# design.net
KiCad netlist of a schematic drawn in Altium Designer
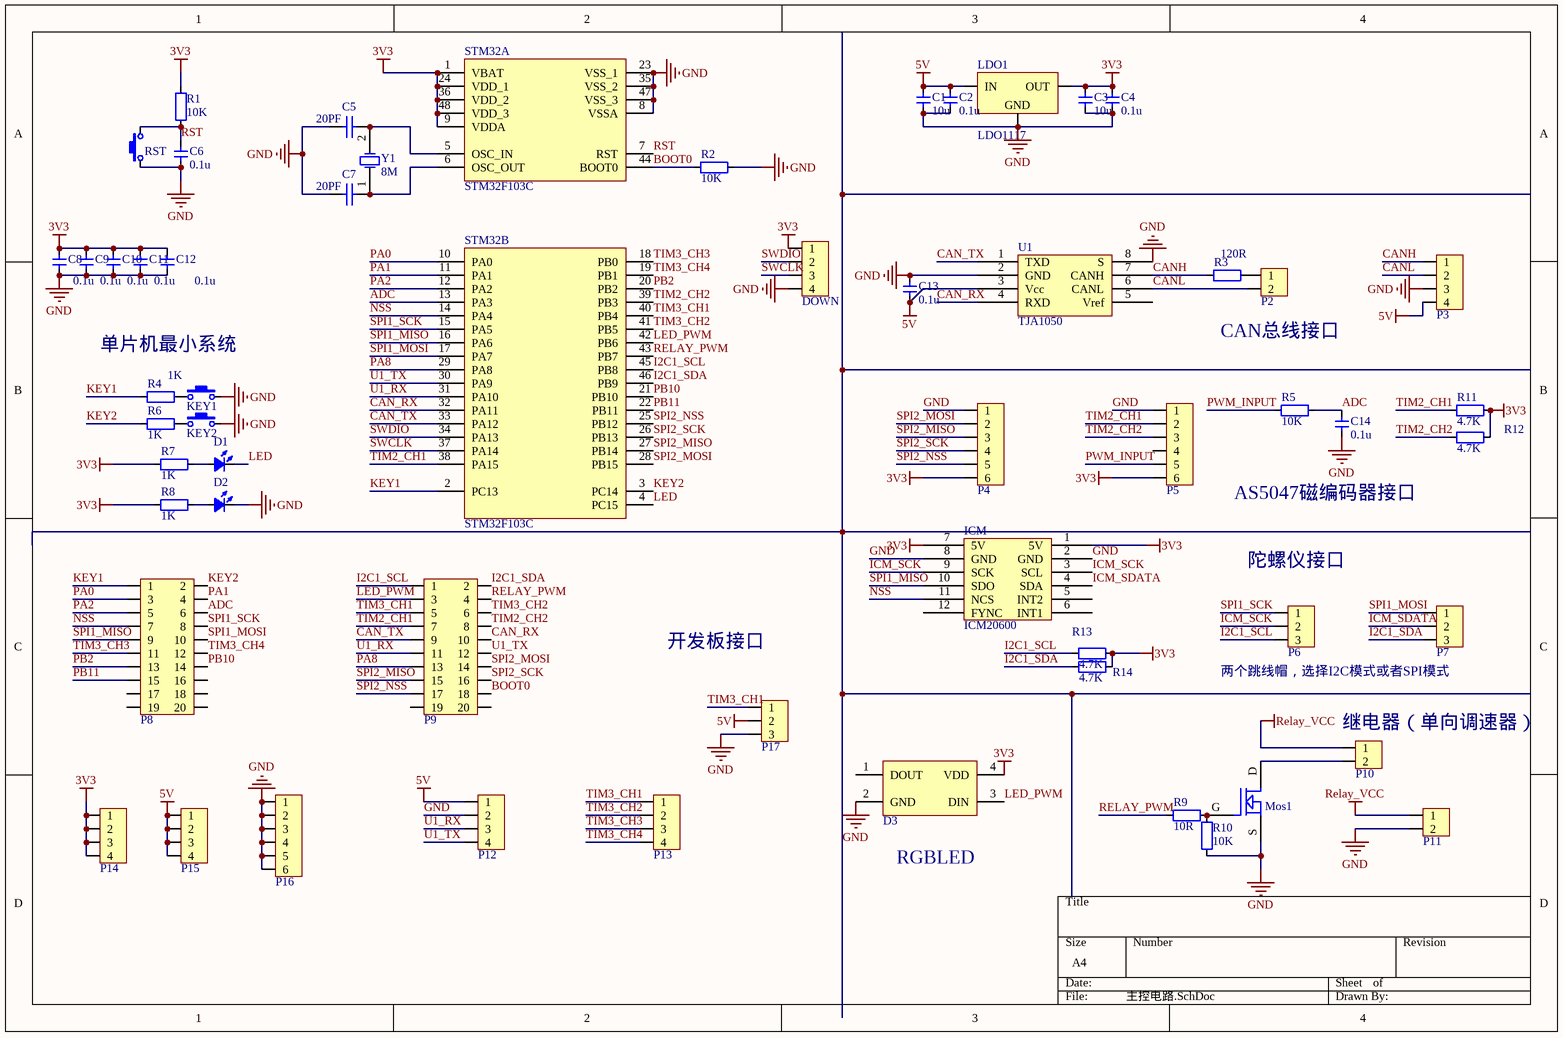
[diagram p0: 主控电路.SchDoc]

(export (version "E")
  (design (tool "Eeschema 10.0.6"))
  (components
    (comp (ref "C1")
      (value "10u")
      (footprint "CAP_0805")
      (description "Capacitor")
      (fields (field (name "Comment") "CAP_0805"))
      (libsource (lib "SCH_Passive") (part "CAP_0805"))
    )
    (comp (ref "C2")
      (value "0.1u")
      (footprint "CAP_0805")
      (description "Capacitor")
      (fields (field (name "Comment") "CAP_0805"))
      (libsource (lib "SCH_Passive") (part "CAP_0805"))
    )
    (comp (ref "C3")
      (value "10u")
      (footprint "CAP_0805")
      (description "Capacitor")
      (fields (field (name "Comment") "CAP_0805"))
      (libsource (lib "SCH_Passive") (part "CAP_0805"))
    )
    (comp (ref "C4")
      (value "0.1u")
      (footprint "CAP_0805")
      (description "Capacitor")
      (fields (field (name "Comment") "CAP_0805"))
      (libsource (lib "SCH_Passive") (part "CAP_0805"))
    )
    (comp (ref "C5")
      (value "20PF")
      (footprint "CAP_0805")
      (description "Capacitor")
      (fields (field (name "Comment") "Cap") (field (name "PUBLISHER") "Altium Limited"))
      (libsource (lib "K60-mainboard-v3.1") (part "Cap_1"))
    )
    (comp (ref "C6")
      (value "0.1u")
      (footprint "CAP_0805")
      (description "Capacitor")
      (fields (field (name "Comment") "CAP_0805"))
      (libsource (lib "SCH_Passive") (part "CAP_0805"))
    )
    (comp (ref "C7")
      (value "20PF")
      (footprint "CAP_0805")
      (description "Capacitor")
      (fields (field (name "Comment") "Cap") (field (name "PUBLISHER") "Altium Limited"))
      (libsource (lib "K60-mainboard-v3.1") (part "Cap_1"))
    )
    (comp (ref "C8")
      (value "0.1u")
      (footprint "CAP_0805")
      (description "Capacitor")
      (fields (field (name "Comment") "CAP_0805"))
      (libsource (lib "SCH_Passive") (part "CAP_0805"))
    )
    (comp (ref "C9")
      (value "0.1u")
      (footprint "CAP_0805")
      (description "Capacitor")
      (fields (field (name "Comment") "CAP_0805"))
      (libsource (lib "SCH_Passive") (part "CAP_0805"))
    )
    (comp (ref "C10")
      (value "0.1u")
      (footprint "CAP_0805")
      (description "Capacitor")
      (fields (field (name "Comment") "CAP_0805"))
      (libsource (lib "SCH_Passive") (part "CAP_0805"))
    )
    (comp (ref "C11")
      (value "0.1u")
      (footprint "CAP_0805")
      (description "Capacitor")
      (fields (field (name "Comment") "CAP_0805"))
      (libsource (lib "SCH_Passive") (part "CAP_0805"))
    )
    (comp (ref "C12")
      (value "0.1u")
      (footprint "CAP_0805")
      (description "Capacitor")
      (fields (field (name "Comment") "CAP_0805"))
      (libsource (lib "SCH_Passive") (part "CAP_0805"))
    )
    (comp (ref "C13")
      (value "0.1u")
      (footprint "CAP_0805")
      (description "Capacitor")
      (fields (field (name "Comment") "CAP_0805"))
      (libsource (lib "SCH_Passive") (part "CAP_0805"))
    )
    (comp (ref "C14")
      (value "0.1u")
      (footprint "CAP_0805")
      (description "Capacitor")
      (fields (field (name "Comment") "CAP_0805"))
      (libsource (lib "SCH_Passive") (part "CAP_0805"))
    )
    (comp (ref "D1")
      (value "LED_0805")
      (footprint "PCB_ActiveLED:LED_0805_RED")
      (description "LED")
      (libsource (lib "SCH_Active") (part "LED_0805"))
    )
    (comp (ref "D2")
      (value "LED_0805")
      (footprint "PCB_ActiveLED:LED_0805_RED")
      (description "LED")
      (libsource (lib "SCH_Active") (part "LED_0805"))
    )
    (comp (ref "D3")
      (value "LED_3535_SK6812")
      (footprint "PCB_ActiveLED:LED_3535_4P")
      (description "LED")
      (libsource (lib "SCH_Active") (part "LED_3535_SK6812"))
    )
    (comp (ref "DOWN")
      (value "HDR1x4_2.54")
      (footprint "PCB_ConnectorHDR:HDR1x4_2.54_180")
      (description "Header")
      (libsource (lib "SCH_ConnectorHDR") (part "HDR1x4_2.54"))
    )
    (comp (ref "ICM")
      (value "ICM20600")
      (footprint "ICM20600模块")
      (libsource (lib "SCH_Module") (part "ICM20600"))
    )
    (comp (ref "KEY1")
      (value "ButtonTACT_3x6x2.5_180")
      (footprint "PCB_Switch:ButtonTACT_3x6x2.5_180")
      (description "Button")
      (libsource (lib "SCH_Switch") (part "ButtonTACT_3x6x2.5_180"))
    )
    (comp (ref "KEY2")
      (value "ButtonTACT_3x6x2.5_180")
      (footprint "PCB_Switch:ButtonTACT_3x6x2.5_180")
      (description "Button")
      (libsource (lib "SCH_Switch") (part "ButtonTACT_3x6x2.5_180"))
    )
    (comp (ref "LDO1")
      (value "LDO1117")
      (footprint "PCB_IntegratedCircuit:SOT223-3")
      (description "Power")
      (libsource (lib "SCH_IntegratedCircuit") (part "LDO1117"))
    )
    (comp (ref "Mos1")
      (value "MOSFET N")
      (footprint "Nmos_SOT23")
      (description "MOS SOT23")
      (libsource (lib "SCH_Active") (part "MOSFET N"))
    )
    (comp (ref "P2")
      (value "HDR1x2_2.54")
      (footprint "PCB_ConnectorHDR:HDR1X2_2.54_180")
      (description "Header")
      (libsource (lib "SCH_ConnectorHDR") (part "HDR1x2_2.54"))
    )
    (comp (ref "P3")
      (value "HDR1x4_2.54")
      (footprint "PCB_ConnectorHDR:HDR1x4_2.54_180")
      (description "Header")
      (libsource (lib "SCH_ConnectorHDR") (part "HDR1x4_2.54"))
    )
    (comp (ref "P4")
      (value "HDR1x6_2.54")
      (footprint "PCB_ConnectorHDR:1.25mm_1X6_SMT")
      (description "Header")
      (libsource (lib "SCH_ConnectorHDR") (part "HDR1x6_2.54"))
    )
    (comp (ref "P5")
      (value "HDR1x6_2.54")
      (footprint "PCB_ConnectorHDR:1.25mm_1X6_SMT")
      (description "Header")
      (libsource (lib "SCH_ConnectorHDR") (part "HDR1x6_2.54"))
    )
    (comp (ref "P6")
      (value "HDR1x3_2.54")
      (footprint "PCB_ConnectorHDR:HDR1X3_2.54_180")
      (description "Header")
      (libsource (lib "SCH_ConnectorHDR") (part "HDR1x3_2.54"))
    )
    (comp (ref "P7")
      (value "HDR1x3_2.54")
      (footprint "PCB_ConnectorHDR:HDR1X3_2.54_180")
      (description "Header")
      (libsource (lib "SCH_ConnectorHDR") (part "HDR1x3_2.54"))
    )
    (comp (ref "P8")
      (value "HDR2x10_2.54")
      (footprint "PCB_ConnectorHDR:HDR2X10_2.54_180")
      (description "Header")
      (libsource (lib "SCH_ConnectorHDR") (part "HDR2x10_2.54"))
    )
    (comp (ref "P9")
      (value "HDR2x10_2.54")
      (footprint "PCB_ConnectorHDR:HDR2X10_2.54_180")
      (description "Header")
      (libsource (lib "SCH_ConnectorHDR") (part "HDR2x10_2.54"))
    )
    (comp (ref "P10")
      (value "HDR1x2_2.54")
      (footprint "PCB_ConnectorHDR:HDR1X2_2.54_180")
      (description "Header")
      (libsource (lib "SCH_ConnectorHDR") (part "HDR1x2_2.54"))
    )
    (comp (ref "P11")
      (value "HDR1x2_2.54")
      (footprint "PCB_ConnectorHDR:HDR1X2_2.54_180")
      (description "Header")
      (libsource (lib "SCH_ConnectorHDR") (part "HDR1x2_2.54"))
    )
    (comp (ref "P12")
      (value "HDR1x4_2.54")
      (footprint "PCB_ConnectorHDR:HDR1x4_2.54_180")
      (description "Header")
      (libsource (lib "SCH_ConnectorHDR") (part "HDR1x4_2.54"))
    )
    (comp (ref "P13")
      (value "HDR1x4_2.54")
      (footprint "PCB_ConnectorHDR:HDR1x4_2.54_180")
      (description "Header")
      (libsource (lib "SCH_ConnectorHDR") (part "HDR1x4_2.54"))
    )
    (comp (ref "P14")
      (value "HDR1x4_2.54")
      (footprint "PCB_ConnectorHDR:HDR1x4_2.54_180")
      (description "Header")
      (libsource (lib "SCH_ConnectorHDR") (part "HDR1x4_2.54"))
    )
    (comp (ref "P15")
      (value "HDR1x4_2.54")
      (footprint "PCB_ConnectorHDR:HDR1x4_2.54_180")
      (description "Header")
      (libsource (lib "SCH_ConnectorHDR") (part "HDR1x4_2.54"))
    )
    (comp (ref "P16")
      (value "HDR1x6_2.54")
      (footprint "PCB_ConnectorHDR:HDR1X6_2.54_180")
      (description "Header")
      (libsource (lib "SCH_ConnectorHDR") (part "HDR1x6_2.54"))
    )
    (comp (ref "P17")
      (value "HDR1x3_2.54")
      (footprint "PCB_ConnectorHDR:HDR1X3_2.54_180")
      (description "Header")
      (libsource (lib "SCH_ConnectorHDR") (part "HDR1x3_2.54"))
    )
    (comp (ref "R1")
      (value "10K")
      (footprint "PCB_PassiveRes:RES_0805")
      (description "Resistor")
      (fields (field (name "Comment") "RES_0805"))
      (libsource (lib "") (part "Res_0805_3"))
    )
    (comp (ref "R2")
      (value "10K")
      (footprint "PCB_PassiveRes:RES_0805")
      (description "Resistor")
      (fields (field (name "Comment") "RES_0805"))
      (libsource (lib "SCH_Passive") (part "Res_0805"))
    )
    (comp (ref "R3")
      (value "120R")
      (footprint "PCB_PassiveRes:RES_0805")
      (description "Resistor")
      (fields (field (name "Comment") "RES_0805"))
      (libsource (lib "SCH_Passive") (part "Res_0805"))
    )
    (comp (ref "R4")
      (value "1K")
      (footprint "PCB_PassiveRes:RES_0805")
      (description "Resistor")
      (fields (field (name "Comment") "RES_0805"))
      (libsource (lib "SCH_Passive") (part "Res_0805"))
    )
    (comp (ref "R5")
      (value "10K")
      (footprint "PCB_PassiveRes:RES_0805")
      (description "Resistor")
      (fields (field (name "Comment") "RES_0805"))
      (libsource (lib "") (part "Res_0805_2"))
    )
    (comp (ref "R6")
      (value "1K")
      (footprint "PCB_PassiveRes:RES_0805")
      (description "Resistor")
      (fields (field (name "Comment") "RES_0805"))
      (libsource (lib "SCH_Passive") (part "Res_0805"))
    )
    (comp (ref "R7")
      (value "1K")
      (footprint "PCB_PassiveRes:RES_0805")
      (description "Resistor")
      (fields (field (name "Comment") "RES_0805"))
      (libsource (lib "SCH_Passive") (part "Res_0805"))
    )
    (comp (ref "R8")
      (value "1K")
      (footprint "PCB_PassiveRes:RES_0805")
      (description "Resistor")
      (fields (field (name "Comment") "RES_0805"))
      (libsource (lib "SCH_Passive") (part "Res_0805"))
    )
    (comp (ref "R9")
      (value "10R")
      (footprint "PCB_PassiveRes:RES_0805")
      (description "Resistor")
      (fields (field (name "Comment") "RES_0805"))
      (libsource (lib "") (part "Res_0805_2"))
    )
    (comp (ref "R10")
      (value "10K")
      (footprint "PCB_PassiveRes:RES_0805")
      (description "Resistor")
      (fields (field (name "Comment") "RES_0805"))
      (libsource (lib "") (part "Res_0805_1"))
    )
    (comp (ref "R11")
      (value "4.7K")
      (footprint "PCB_PassiveRes:RES_0805")
      (description "Resistor")
      (fields (field (name "Comment") "RES_0805"))
      (libsource (lib "") (part "Res_0805_2"))
    )
    (comp (ref "R12")
      (value "4.7K")
      (footprint "PCB_PassiveRes:RES_0805")
      (description "Resistor")
      (fields (field (name "Comment") "RES_0805"))
      (libsource (lib "") (part "Res_0805_2"))
    )
    (comp (ref "R13")
      (value "4.7K")
      (footprint "PCB_PassiveRes:RES_0805")
      (description "Resistor")
      (fields (field (name "Comment") "RES_0805"))
      (libsource (lib "") (part "Res_0805_2"))
    )
    (comp (ref "R14")
      (value "4.7K")
      (footprint "PCB_PassiveRes:RES_0805")
      (description "Resistor")
      (fields (field (name "Comment") "RES_0805"))
      (libsource (lib "") (part "Res_0805_2"))
    )
    (comp (ref "RST")
      (value "ButtonTACT_3x6x2.5_180")
      (footprint "PCB_Switch:ButtonTACT_3x6x2.5_180")
      (description "Button")
      (libsource (lib "SCH_Switch") (part "ButtonTACT_3x6x2.5_180"))
    )
    (comp (ref "STM32")
      (value "STM32F103C")
      (footprint "PCB_IntegratedCircuit:LQFP_P0.5_48")
      (description "MCU")
      (libsource (lib "SCH_IntegratedCircuit") (part "STM32F103C"))
    )
    (comp (ref "U1")
      (value "TJA1050")
      (footprint "SOP_E150_8")
      (libsource (lib "SCH_IntegratedCircuit") (part "TJA1050"))
    )
    (comp (ref "Y1")
      (value "8M")
      (footprint "Osc-6032")
      (description "Crystal Oscillator")
      (fields (field (name "PUBLISHER") "Altium Limited"))
      (libsource (lib "Libraries_2014_0618") (part "C-Osc"))
    )
  )
  (nets
    (net (code "1") (name "/ADC") (class "Default")
      (node (ref "C14") (pin "2") (pinfunction "2_2") (pintype "passive"))
      (node (ref "P8") (pin "6") (pinfunction "6_6") (pintype "passive"))
      (node (ref "R5") (pin "1") (pinfunction "1_1") (pintype "passive"))
      (node (ref "STM32") (pin "13") (pinfunction "PA3_13") (pintype "passive"))
    )
    (net (code "2") (name "/BOOT0") (class "Default")
      (node (ref "P9") (pin "18") (pinfunction "18_18") (pintype "passive"))
      (node (ref "R2") (pin "1") (pinfunction "1_1") (pintype "passive"))
      (node (ref "STM32") (pin "44") (pinfunction "BOOT0_44") (pintype "passive"))
    )
    (net (code "3") (name "/CANH") (class "Default")
      (node (ref "P3") (pin "1") (pinfunction "1_1") (pintype "passive"))
      (node (ref "R3") (pin "1") (pinfunction "1_1") (pintype "passive"))
      (node (ref "U1") (pin "7") (pinfunction "CANH_7") (pintype "passive"))
    )
    (net (code "4") (name "/CANL") (class "Default")
      (node (ref "P2") (pin "2") (pinfunction "2_2") (pintype "passive"))
      (node (ref "P3") (pin "2") (pinfunction "2_2") (pintype "passive"))
      (node (ref "U1") (pin "6") (pinfunction "CANL_6") (pintype "passive"))
    )
    (net (code "5") (name "/CAN_RX") (class "Default")
      (node (ref "P9") (pin "10") (pinfunction "10_10") (pintype "passive"))
      (node (ref "STM32") (pin "32") (pinfunction "PA11_32") (pintype "passive"))
      (node (ref "U1") (pin "4") (pinfunction "RXD_4") (pintype "passive"))
    )
    (net (code "6") (name "/CAN_TX") (class "Default")
      (node (ref "P9") (pin "9") (pinfunction "9_9") (pintype "passive"))
      (node (ref "STM32") (pin "33") (pinfunction "PA12_33") (pintype "passive"))
      (node (ref "U1") (pin "1") (pinfunction "TXD_1") (pintype "passive"))
    )
    (net (code "7") (name "/I2C1_SCL") (class "Default")
      (node (ref "P6") (pin "3") (pinfunction "3_3") (pintype "passive"))
      (node (ref "P9") (pin "1") (pinfunction "1_1") (pintype "passive"))
      (node (ref "R13") (pin "2") (pinfunction "2_2") (pintype "passive"))
      (node (ref "STM32") (pin "45") (pinfunction "PB8_45") (pintype "passive"))
    )
    (net (code "8") (name "/I2C1_SDA") (class "Default")
      (node (ref "P7") (pin "3") (pinfunction "3_3") (pintype "passive"))
      (node (ref "P9") (pin "2") (pinfunction "2_2") (pintype "passive"))
      (node (ref "R14") (pin "2") (pinfunction "2_2") (pintype "passive"))
      (node (ref "STM32") (pin "46") (pinfunction "PB9_46") (pintype "passive"))
    )
    (net (code "9") (name "/ICM_SCK") (class "Default")
      (node (ref "ICM") (pin "3") (pinfunction "SCL_3") (pintype "passive"))
      (node (ref "ICM") (pin "9") (pinfunction "SCK_9") (pintype "passive"))
      (node (ref "P6") (pin "2") (pinfunction "2_2") (pintype "passive"))
    )
    (net (code "10") (name "/ICM_SDATA") (class "Default")
      (node (ref "ICM") (pin "4") (pinfunction "SDA_4") (pintype "passive"))
      (node (ref "P7") (pin "2") (pinfunction "2_2") (pintype "passive"))
    )
    (net (code "11") (name "/KEY1") (class "Default")
      (node (ref "P8") (pin "1") (pinfunction "1_1") (pintype "passive"))
      (node (ref "R4") (pin "1") (pinfunction "1_1") (pintype "passive"))
      (node (ref "STM32") (pin "2") (pinfunction "PC13_2") (pintype "passive"))
    )
    (net (code "12") (name "/KEY2") (class "Default")
      (node (ref "P8") (pin "2") (pinfunction "2_2") (pintype "passive"))
      (node (ref "R6") (pin "1") (pinfunction "1_1") (pintype "passive"))
      (node (ref "STM32") (pin "3") (pinfunction "PC14_3") (pintype "passive"))
    )
    (net (code "13") (name "/LED") (class "Default")
      (node (ref "D1") (pin "2") (pinfunction "K_2") (pintype "passive"))
      (node (ref "STM32") (pin "4") (pinfunction "PC15_4") (pintype "passive"))
    )
    (net (code "14") (name "/LED_PWM") (class "Default")
      (node (ref "D3") (pin "3") (pinfunction "DIN_3") (pintype "passive"))
      (node (ref "P9") (pin "3") (pinfunction "3_3") (pintype "passive"))
      (node (ref "STM32") (pin "42") (pinfunction "PB6_42") (pintype "passive"))
    )
    (net (code "15") (name "/NSS") (class "Default")
      (node (ref "ICM") (pin "11") (pinfunction "NCS_11") (pintype "passive"))
      (node (ref "P8") (pin "7") (pinfunction "7_7") (pintype "passive"))
      (node (ref "STM32") (pin "14") (pinfunction "PA4_14") (pintype "passive"))
    )
    (net (code "16") (name "/PA0") (class "Default")
      (node (ref "P8") (pin "3") (pinfunction "3_3") (pintype "passive"))
      (node (ref "STM32") (pin "10") (pinfunction "PA0_10") (pintype "passive"))
    )
    (net (code "17") (name "/PA1") (class "Default")
      (node (ref "P8") (pin "4") (pinfunction "4_4") (pintype "passive"))
      (node (ref "STM32") (pin "11") (pinfunction "PA1_11") (pintype "passive"))
    )
    (net (code "18") (name "/PA2") (class "Default")
      (node (ref "P8") (pin "5") (pinfunction "5_5") (pintype "passive"))
      (node (ref "STM32") (pin "12") (pinfunction "PA2_12") (pintype "passive"))
    )
    (net (code "19") (name "/PA8") (class "Default")
      (node (ref "P9") (pin "13") (pinfunction "13_13") (pintype "passive"))
      (node (ref "STM32") (pin "29") (pinfunction "PA8_29") (pintype "passive"))
    )
    (net (code "20") (name "/PB2") (class "Default")
      (node (ref "P8") (pin "13") (pinfunction "13_13") (pintype "passive"))
      (node (ref "STM32") (pin "20") (pinfunction "PB2_20") (pintype "passive"))
    )
    (net (code "21") (name "/PB10") (class "Default")
      (node (ref "P8") (pin "14") (pinfunction "14_14") (pintype "passive"))
      (node (ref "STM32") (pin "21") (pinfunction "PB10_21") (pintype "passive"))
    )
    (net (code "22") (name "/PB11") (class "Default")
      (node (ref "P8") (pin "15") (pinfunction "15_15") (pintype "passive"))
      (node (ref "STM32") (pin "22") (pinfunction "PB11_22") (pintype "passive"))
    )
    (net (code "23") (name "/PWM_INPUT") (class "Default")
      (node (ref "P5") (pin "5") (pinfunction "5_5") (pintype "passive"))
      (node (ref "R5") (pin "2") (pinfunction "2_2") (pintype "passive"))
    )
    (net (code "24") (name "/RELAY_PWM") (class "Default")
      (node (ref "P9") (pin "4") (pinfunction "4_4") (pintype "passive"))
      (node (ref "R9") (pin "2") (pinfunction "2_2") (pintype "passive"))
      (node (ref "STM32") (pin "43") (pinfunction "PB7_43") (pintype "passive"))
    )
    (net (code "25") (name "/RST") (class "Default")
      (node (ref "C6") (pin "2") (pinfunction "2_2") (pintype "passive"))
      (node (ref "R1") (pin "1") (pinfunction "1_1") (pintype "passive"))
      (node (ref "RST") (pin "2") (pinfunction "2_2") (pintype "passive"))
      (node (ref "STM32") (pin "7") (pinfunction "RST_7") (pintype "passive"))
    )
    (net (code "26") (name "/SPI1_MISO") (class "Default")
      (node (ref "ICM") (pin "10") (pinfunction "SDO_10") (pintype "passive"))
      (node (ref "P8") (pin "9") (pinfunction "9_9") (pintype "passive"))
      (node (ref "STM32") (pin "16") (pinfunction "PA6_16") (pintype "passive"))
    )
    (net (code "27") (name "/SPI1_MOSI") (class "Default")
      (node (ref "P7") (pin "1") (pinfunction "1_1") (pintype "passive"))
      (node (ref "P8") (pin "10") (pinfunction "10_10") (pintype "passive"))
      (node (ref "STM32") (pin "17") (pinfunction "PA7_17") (pintype "passive"))
    )
    (net (code "28") (name "/SPI1_SCK") (class "Default")
      (node (ref "P6") (pin "1") (pinfunction "1_1") (pintype "passive"))
      (node (ref "P8") (pin "8") (pinfunction "8_8") (pintype "passive"))
      (node (ref "STM32") (pin "15") (pinfunction "PA5_15") (pintype "passive"))
    )
    (net (code "29") (name "/SPI2_MISO") (class "Default")
      (node (ref "P4") (pin "3") (pinfunction "3_3") (pintype "passive"))
      (node (ref "P9") (pin "15") (pinfunction "15_15") (pintype "passive"))
      (node (ref "STM32") (pin "27") (pinfunction "PB14_27") (pintype "passive"))
    )
    (net (code "30") (name "/SPI2_MOSI") (class "Default")
      (node (ref "P4") (pin "2") (pinfunction "2_2") (pintype "passive"))
      (node (ref "P9") (pin "14") (pinfunction "14_14") (pintype "passive"))
      (node (ref "STM32") (pin "28") (pinfunction "PB15_28") (pintype "passive"))
    )
    (net (code "31") (name "/SPI2_NSS") (class "Default")
      (node (ref "P4") (pin "5") (pinfunction "5_5") (pintype "passive"))
      (node (ref "P9") (pin "17") (pinfunction "17_17") (pintype "passive"))
      (node (ref "STM32") (pin "25") (pinfunction "PB12_25") (pintype "passive"))
    )
    (net (code "32") (name "/SPI2_SCK") (class "Default")
      (node (ref "P4") (pin "4") (pinfunction "4_4") (pintype "passive"))
      (node (ref "P9") (pin "16") (pinfunction "16_16") (pintype "passive"))
      (node (ref "STM32") (pin "26") (pinfunction "PB13_26") (pintype "passive"))
    )
    (net (code "33") (name "/SWCLK") (class "Default")
      (node (ref "DOWN") (pin "3") (pinfunction "3_3") (pintype "passive"))
      (node (ref "STM32") (pin "37") (pinfunction "PA14_37") (pintype "passive"))
    )
    (net (code "34") (name "/SWDIO") (class "Default")
      (node (ref "DOWN") (pin "2") (pinfunction "2_2") (pintype "passive"))
      (node (ref "STM32") (pin "34") (pinfunction "PA13_34") (pintype "passive"))
    )
    (net (code "35") (name "/TIM2_CH1") (class "Default")
      (node (ref "P5") (pin "2") (pinfunction "2_2") (pintype "passive"))
      (node (ref "P9") (pin "7") (pinfunction "7_7") (pintype "passive"))
      (node (ref "R11") (pin "2") (pinfunction "2_2") (pintype "passive"))
      (node (ref "STM32") (pin "38") (pinfunction "PA15_38") (pintype "passive"))
    )
    (net (code "36") (name "/TIM2_CH2") (class "Default")
      (node (ref "P5") (pin "3") (pinfunction "3_3") (pintype "passive"))
      (node (ref "P9") (pin "8") (pinfunction "8_8") (pintype "passive"))
      (node (ref "R12") (pin "2") (pinfunction "2_2") (pintype "passive"))
      (node (ref "STM32") (pin "39") (pinfunction "PB3_39") (pintype "passive"))
    )
    (net (code "37") (name "/TIM3_CH1") (class "Default")
      (node (ref "P13") (pin "1") (pinfunction "1_1") (pintype "passive"))
      (node (ref "P17") (pin "1") (pinfunction "1_1") (pintype "passive"))
      (node (ref "P9") (pin "5") (pinfunction "5_5") (pintype "passive"))
      (node (ref "STM32") (pin "40") (pinfunction "PB4_40") (pintype "passive"))
    )
    (net (code "38") (name "/TIM3_CH2") (class "Default")
      (node (ref "P13") (pin "2") (pinfunction "2_2") (pintype "passive"))
      (node (ref "P9") (pin "6") (pinfunction "6_6") (pintype "passive"))
      (node (ref "STM32") (pin "41") (pinfunction "PB5_41") (pintype "passive"))
    )
    (net (code "39") (name "/TIM3_CH3") (class "Default")
      (node (ref "P13") (pin "3") (pinfunction "3_3") (pintype "passive"))
      (node (ref "P8") (pin "11") (pinfunction "11_11") (pintype "passive"))
      (node (ref "STM32") (pin "18") (pinfunction "PB0_18") (pintype "passive"))
    )
    (net (code "40") (name "/TIM3_CH4") (class "Default")
      (node (ref "P13") (pin "4") (pinfunction "4_4") (pintype "passive"))
      (node (ref "P8") (pin "12") (pinfunction "12_12") (pintype "passive"))
      (node (ref "STM32") (pin "19") (pinfunction "PB1_19") (pintype "passive"))
    )
    (net (code "41") (name "/U1_RX") (class "Default")
      (node (ref "P12") (pin "3") (pinfunction "3_3") (pintype "passive"))
      (node (ref "P9") (pin "11") (pinfunction "11_11") (pintype "passive"))
      (node (ref "STM32") (pin "31") (pinfunction "PA10_31") (pintype "passive"))
    )
    (net (code "42") (name "/U1_TX") (class "Default")
      (node (ref "P12") (pin "4") (pinfunction "4_4") (pintype "passive"))
      (node (ref "P9") (pin "12") (pinfunction "12_12") (pintype "passive"))
      (node (ref "STM32") (pin "30") (pinfunction "PA9_30") (pintype "passive"))
    )
    (net (code "43") (name "3V3") (class "Default")
      (node (ref "C10") (pin "2") (pinfunction "2_2") (pintype "passive"))
      (node (ref "C11") (pin "2") (pinfunction "2_2") (pintype "passive"))
      (node (ref "C12") (pin "2") (pinfunction "2_2") (pintype "passive"))
      (node (ref "C3") (pin "2") (pinfunction "2_2") (pintype "passive"))
      (node (ref "C4") (pin "2") (pinfunction "2_2") (pintype "passive"))
      (node (ref "C8") (pin "2") (pinfunction "2_2") (pintype "passive"))
      (node (ref "C9") (pin "2") (pinfunction "2_2") (pintype "passive"))
      (node (ref "D3") (pin "4") (pinfunction "VDD_4") (pintype "passive"))
      (node (ref "DOWN") (pin "1") (pinfunction "1_1") (pintype "passive"))
      (node (ref "ICM") (pin "1") (pinfunction "5V_1") (pintype "passive"))
      (node (ref "ICM") (pin "7") (pinfunction "5V_7") (pintype "passive"))
      (node (ref "LDO1") (pin "2") (pinfunction "OUT_2") (pintype "power_in"))
      (node (ref "P14") (pin "1") (pinfunction "1_1") (pintype "passive"))
      (node (ref "P14") (pin "2") (pinfunction "2_2") (pintype "passive"))
      (node (ref "P14") (pin "3") (pinfunction "3_3") (pintype "passive"))
      (node (ref "P14") (pin "4") (pinfunction "4_4") (pintype "passive"))
      (node (ref "P4") (pin "6") (pinfunction "6_6") (pintype "passive"))
      (node (ref "P5") (pin "6") (pinfunction "6_6") (pintype "passive"))
      (node (ref "R1") (pin "2") (pinfunction "2_2") (pintype "passive"))
      (node (ref "R11") (pin "1") (pinfunction "1_1") (pintype "passive"))
      (node (ref "R12") (pin "1") (pinfunction "1_1") (pintype "passive"))
      (node (ref "R13") (pin "1") (pinfunction "1_1") (pintype "passive"))
      (node (ref "R14") (pin "1") (pinfunction "1_1") (pintype "passive"))
      (node (ref "R7") (pin "1") (pinfunction "1_1") (pintype "passive"))
      (node (ref "R8") (pin "1") (pinfunction "1_1") (pintype "passive"))
      (node (ref "STM32") (pin "1") (pinfunction "VBAT_1") (pintype "passive"))
      (node (ref "STM32") (pin "24") (pinfunction "VDD_1_24") (pintype "passive"))
      (node (ref "STM32") (pin "36") (pinfunction "VDD_2_36") (pintype "passive"))
      (node (ref "STM32") (pin "48") (pinfunction "VDD_3_48") (pintype "passive"))
      (node (ref "STM32") (pin "9") (pinfunction "VDDA_9") (pintype "passive"))
    )
    (net (code "44") (name "5V") (class "Default")
      (node (ref "C1") (pin "2") (pinfunction "2_2") (pintype "passive"))
      (node (ref "C13") (pin "1") (pinfunction "1_1") (pintype "passive"))
      (node (ref "C2") (pin "2") (pinfunction "2_2") (pintype "passive"))
      (node (ref "LDO1") (pin "3") (pinfunction "IN_3") (pintype "power_in"))
      (node (ref "P12") (pin "1") (pinfunction "1_1") (pintype "passive"))
      (node (ref "P15") (pin "1") (pinfunction "1_1") (pintype "passive"))
      (node (ref "P15") (pin "2") (pinfunction "2_2") (pintype "passive"))
      (node (ref "P15") (pin "3") (pinfunction "3_3") (pintype "passive"))
      (node (ref "P15") (pin "4") (pinfunction "4_4") (pintype "passive"))
      (node (ref "P17") (pin "2") (pinfunction "2_2") (pintype "passive"))
      (node (ref "P3") (pin "4") (pinfunction "4_4") (pintype "passive"))
      (node (ref "U1") (pin "3") (pinfunction "Vcc_3") (pintype "passive"))
    )
    (net (code "45") (name "GND") (class "Default")
      (node (ref "C1") (pin "1") (pinfunction "1_1") (pintype "passive"))
      (node (ref "C10") (pin "1") (pinfunction "1_1") (pintype "passive"))
      (node (ref "C11") (pin "1") (pinfunction "1_1") (pintype "passive"))
      (node (ref "C12") (pin "1") (pinfunction "1_1") (pintype "passive"))
      (node (ref "C13") (pin "2") (pinfunction "2_2") (pintype "passive"))
      (node (ref "C14") (pin "1") (pinfunction "1_1") (pintype "passive"))
      (node (ref "C2") (pin "1") (pinfunction "1_1") (pintype "passive"))
      (node (ref "C3") (pin "1") (pinfunction "1_1") (pintype "passive"))
      (node (ref "C4") (pin "1") (pinfunction "1_1") (pintype "passive"))
      (node (ref "C5") (pin "1") (pinfunction "1_1") (pintype "passive"))
      (node (ref "C6") (pin "1") (pinfunction "1_1") (pintype "passive"))
      (node (ref "C7") (pin "1") (pinfunction "1_1") (pintype "passive"))
      (node (ref "C8") (pin "1") (pinfunction "1_1") (pintype "passive"))
      (node (ref "C9") (pin "1") (pinfunction "1_1") (pintype "passive"))
      (node (ref "D2") (pin "2") (pinfunction "K_2") (pintype "passive"))
      (node (ref "D3") (pin "2") (pinfunction "GND_2") (pintype "passive"))
      (node (ref "DOWN") (pin "4") (pinfunction "4_4") (pintype "passive"))
      (node (ref "ICM") (pin "2") (pinfunction "GND_2") (pintype "passive"))
      (node (ref "ICM") (pin "8") (pinfunction "GND_8") (pintype "passive"))
      (node (ref "KEY1") (pin "2") (pinfunction "2_2") (pintype "passive"))
      (node (ref "KEY2") (pin "2") (pinfunction "2_2") (pintype "passive"))
      (node (ref "LDO1") (pin "1") (pinfunction "GND_1") (pintype "power_in"))
      (node (ref "Mos1") (pin "S") (pinfunction "S_S") (pintype "passive"))
      (node (ref "P11") (pin "2") (pinfunction "2_2") (pintype "passive"))
      (node (ref "P12") (pin "2") (pinfunction "2_2") (pintype "passive"))
      (node (ref "P16") (pin "1") (pinfunction "1_1") (pintype "passive"))
      (node (ref "P16") (pin "2") (pinfunction "2_2") (pintype "passive"))
      (node (ref "P16") (pin "3") (pinfunction "3_3") (pintype "passive"))
      (node (ref "P16") (pin "4") (pinfunction "4_4") (pintype "passive"))
      (node (ref "P16") (pin "5") (pinfunction "5_5") (pintype "passive"))
      (node (ref "P16") (pin "6") (pinfunction "6_6") (pintype "passive"))
      (node (ref "P17") (pin "3") (pinfunction "3_3") (pintype "passive"))
      (node (ref "P3") (pin "3") (pinfunction "3_3") (pintype "passive"))
      (node (ref "P4") (pin "1") (pinfunction "1_1") (pintype "passive"))
      (node (ref "P5") (pin "1") (pinfunction "1_1") (pintype "passive"))
      (node (ref "R10") (pin "2") (pinfunction "2_2") (pintype "passive"))
      (node (ref "R2") (pin "2") (pinfunction "2_2") (pintype "passive"))
      (node (ref "RST") (pin "1") (pinfunction "1_1") (pintype "passive"))
      (node (ref "STM32") (pin "23") (pinfunction "VSS_1_23") (pintype "passive"))
      (node (ref "STM32") (pin "35") (pinfunction "VSS_2_35") (pintype "passive"))
      (node (ref "STM32") (pin "47") (pinfunction "VSS_3_47") (pintype "passive"))
      (node (ref "STM32") (pin "8") (pinfunction "VSSA_8") (pintype "passive"))
      (node (ref "U1") (pin "2") (pinfunction "GND_2") (pintype "passive"))
      (node (ref "U1") (pin "8") (pinfunction "S_8") (pintype "passive"))
    )
    (net (code "46") (name "Net-(D1-A)") (class "Default")
      (node (ref "D1") (pin "1") (pinfunction "A_1") (pintype "passive"))
      (node (ref "R7") (pin "2") (pinfunction "2_2") (pintype "passive"))
    )
    (net (code "47") (name "Net-(D2-A)") (class "Default")
      (node (ref "D2") (pin "1") (pinfunction "A_1") (pintype "passive"))
      (node (ref "R8") (pin "2") (pinfunction "2_2") (pintype "passive"))
    )
    (net (code "48") (name "Net-(KEY1-Pad1)") (class "Default")
      (node (ref "KEY1") (pin "1") (pinfunction "1_1") (pintype "passive"))
      (node (ref "R4") (pin "2") (pinfunction "2_2") (pintype "passive"))
    )
    (net (code "49") (name "Net-(KEY2-Pad1)") (class "Default")
      (node (ref "KEY2") (pin "1") (pinfunction "1_1") (pintype "passive"))
      (node (ref "R6") (pin "2") (pinfunction "2_2") (pintype "passive"))
    )
    (net (code "50") (name "Net-(Mos1-PadD)") (class "Default")
      (node (ref "Mos1") (pin "D") (pinfunction "D_D") (pintype "passive"))
      (node (ref "P10") (pin "2") (pinfunction "2_2") (pintype "passive"))
    )
    (net (code "51") (name "Net-(Mos1-PadG)") (class "Default")
      (node (ref "Mos1") (pin "G") (pinfunction "G_G") (pintype "passive"))
      (node (ref "R10") (pin "1") (pinfunction "1_1") (pintype "passive"))
      (node (ref "R9") (pin "1") (pinfunction "1_1") (pintype "passive"))
    )
    (net (code "52") (name "Net-(P2-Pad1)") (class "Default")
      (node (ref "P2") (pin "1") (pinfunction "1_1") (pintype "passive"))
      (node (ref "R3") (pin "2") (pinfunction "2_2") (pintype "passive"))
    )
    (net (code "53") (name "Net-(STM32A-OSC_IN)") (class "Default")
      (node (ref "C5") (pin "2") (pinfunction "2_2") (pintype "passive"))
      (node (ref "STM32") (pin "5") (pinfunction "OSC_IN_5") (pintype "passive"))
      (node (ref "Y1") (pin "2") (pinfunction "OSC2_2") (pintype "passive"))
    )
    (net (code "54") (name "Net-(STM32A-OSC_OUT)") (class "Default")
      (node (ref "C7") (pin "2") (pinfunction "2_2") (pintype "passive"))
      (node (ref "STM32") (pin "6") (pinfunction "OSC_OUT_6") (pintype "passive"))
      (node (ref "Y1") (pin "1") (pinfunction "OSC1_1") (pintype "passive"))
    )
    (net (code "55") (name "Relay_VCC") (class "Default")
      (node (ref "P10") (pin "1") (pinfunction "1_1") (pintype "passive"))
      (node (ref "P11") (pin "1") (pinfunction "1_1") (pintype "passive"))
    )
    (net (code "56") (name "unconnected-(D3-DOUT-Pad1)") (class "Default")
      (node (ref "D3") (pin "1") (pinfunction "DOUT_1") (pintype "passive"))
    )
    (net (code "57") (name "unconnected-(ICM-FYNC-Pad12)") (class "Default")
      (node (ref "ICM") (pin "12") (pinfunction "FYNC_12") (pintype "passive"))
    )
    (net (code "58") (name "unconnected-(ICM-INT1-Pad6)") (class "Default")
      (node (ref "ICM") (pin "6") (pinfunction "INT1_6") (pintype "passive"))
    )
    (net (code "59") (name "unconnected-(ICM-INT2-Pad5)") (class "Default")
      (node (ref "ICM") (pin "5") (pinfunction "INT2_5") (pintype "passive"))
    )
    (net (code "60") (name "unconnected-(P5-Pad4)") (class "Default")
      (node (ref "P5") (pin "4") (pinfunction "4_4") (pintype "passive"))
    )
    (net (code "61") (name "unconnected-(P8-Pad16)") (class "Default")
      (node (ref "P8") (pin "16") (pinfunction "16_16") (pintype "passive"))
    )
    (net (code "62") (name "unconnected-(P8-Pad17)") (class "Default")
      (node (ref "P8") (pin "17") (pinfunction "17_17") (pintype "passive"))
    )
    (net (code "63") (name "unconnected-(P8-Pad18)") (class "Default")
      (node (ref "P8") (pin "18") (pinfunction "18_18") (pintype "passive"))
    )
    (net (code "64") (name "unconnected-(P8-Pad19)") (class "Default")
      (node (ref "P8") (pin "19") (pinfunction "19_19") (pintype "passive"))
    )
    (net (code "65") (name "unconnected-(P8-Pad20)") (class "Default")
      (node (ref "P8") (pin "20") (pinfunction "20_20") (pintype "passive"))
    )
    (net (code "66") (name "unconnected-(P9-Pad19)") (class "Default")
      (node (ref "P9") (pin "19") (pinfunction "19_19") (pintype "passive"))
    )
    (net (code "67") (name "unconnected-(P9-Pad20)") (class "Default")
      (node (ref "P9") (pin "20") (pinfunction "20_20") (pintype "passive"))
    )
    (net (code "68") (name "unconnected-(U1-Vref-Pad5)") (class "Default")
      (node (ref "U1") (pin "5") (pinfunction "Vref_5") (pintype "passive"))
    )
  )
)
